# ModuleAudioBluetooth.net
KiCad netlist of a schematic drawn in Altium Designer
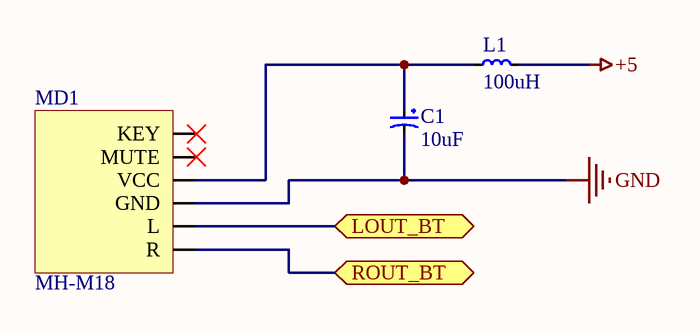
[diagram p0: ModuleAudioBluetooth.SchDoc]

(export (version "E")
  (design (tool "Eeschema 10.0.6"))
  (components
    (comp (ref "C1")
      (value "10uF")
      (footprint "C-ELE-1.5-4X7MM")
      (description "Cac Loai Tu Hoa")
      (libsource (lib "phatvu1294_Lib") (part "CAP-ELE"))
    )
    (comp (ref "L1")
      (value "100uH")
      (footprint "L-PK0406-2-5X8MM")
      (description "Cac Loai Cuon Cam Don")
      (libsource (lib "phatvu1294_Lib") (part "IND"))
    )
    (comp (ref "MD1")
      (value "MH-M18")
      (footprint "MH-M18")
      (description "Module Thu Audio Bluetooth")
      (libsource (lib "phatvu1294_Lib") (part "MH-M18"))
    )
  )
  (nets
    (net (code "1") (name "+5") (class "Default")
      (node (ref "L1") (pin "2") (pinfunction "2_2") (pintype "passive"))
    )
    (net (code "2") (name "/LOUT_BT") (class "Default")
      (node (ref "MD1") (pin "5") (pinfunction "L_5") (pintype "passive"))
    )
    (net (code "3") (name "/ROUT_BT") (class "Default")
      (node (ref "MD1") (pin "6") (pinfunction "R_6") (pintype "passive"))
    )
    (net (code "4") (name "GND") (class "Default")
      (node (ref "C1") (pin "2") (pinfunction "2_2") (pintype "passive"))
      (node (ref "MD1") (pin "4") (pinfunction "GND_4") (pintype "passive"))
    )
    (net (code "5") (name "Net-(MD1-VCC)") (class "Default")
      (node (ref "C1") (pin "1") (pinfunction "1_1") (pintype "passive"))
      (node (ref "L1") (pin "1") (pinfunction "1_1") (pintype "passive"))
      (node (ref "MD1") (pin "3") (pinfunction "VCC_3") (pintype "passive"))
    )
    (net (code "6") (name "unconnected-(MD1-KEY-Pad1)") (class "Default")
      (node (ref "MD1") (pin "1") (pinfunction "KEY_1") (pintype "passive+no_connect"))
    )
    (net (code "7") (name "unconnected-(MD1-MUTE-Pad2)") (class "Default")
      (node (ref "MD1") (pin "2") (pinfunction "MUTE_2") (pintype "passive+no_connect"))
    )
  )
)
